# 4_pin_plank.net
KiCad netlist of a schematic drawn in EAGLE
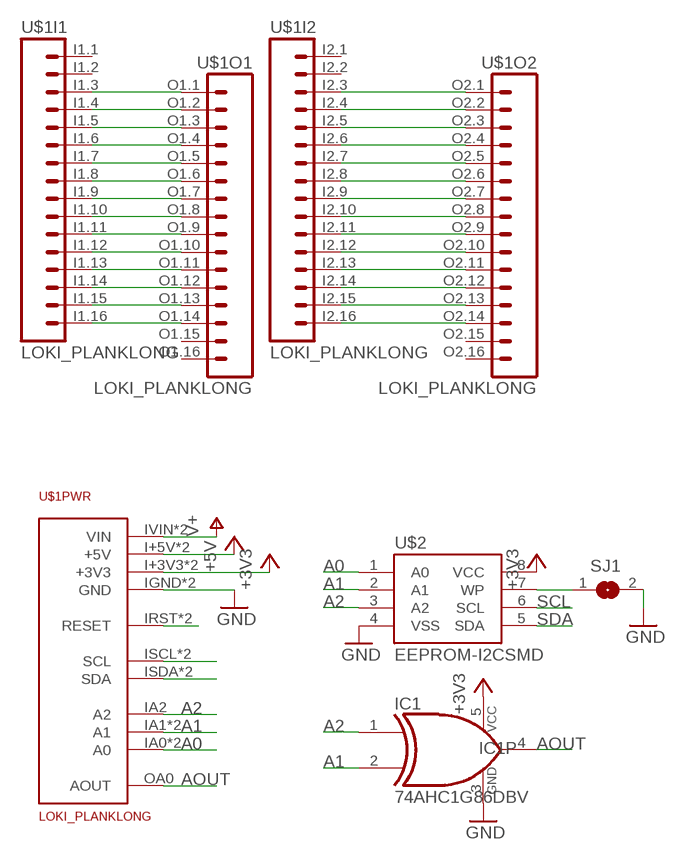
[diagram p0: schematic, sheet 1]

(export (version "E")
  (design (tool "Eeschema 10.0.6"))
  (components
    (comp (ref "IC1")
      (value "74AHC1G86DBV")
      (footprint "eagle-import:SOT23-5")
      (libsource (lib "eagle-import") (part "741G86DBVAHC"))
    )
    (comp (ref "SJ1") (value "SJ") (footprint "eagle-import:SJ") (libsource (lib "eagle-import") (part "SJ")))
    (comp (ref "U$1")
      (value "LOKI_PLANKLONG")
      (footprint "eagle-import:PLANK_LONG")
      (libsource (lib "eagle-import") (part "LOKI_PLANKLONG"))
    )
    (comp (ref "U$2")
      (value "EEPROM-I2CSMD")
      (footprint "eagle-import:SO08")
      (libsource (lib "eagle-import") (part "EEPROM-I2CSMD"))
    )
  )
  (nets
    (net (code "1") (name "+3V3") (class "Default")
      (node (ref "IC1") (pin "5") (pinfunction "VCC_5") (pintype "power_in"))
      (node (ref "U$1") (pin "I+3V3") (pinfunction "+3V3_I+3V3") (pintype "power_in"))
      (node (ref "U$1") (pin "O+3V3") (pinfunction "+3V3_O+3V3") (pintype "power_in"))
      (node (ref "U$2") (pin "8") (pinfunction "VCC_8") (pintype "power_in"))
    )
    (net (code "2") (name "+5V") (class "Default")
      (node (ref "U$1") (pin "I+5V") (pinfunction "+5V_I+5V") (pintype "power_in"))
      (node (ref "U$1") (pin "O+5V") (pinfunction "+5V_O+5V") (pintype "power_in"))
    )
    (net (code "3") (name "/A0") (class "Default")
      (node (ref "U$1") (pin "IA0") (pinfunction "A0_IA0") (pintype "output"))
      (node (ref "U$1") (pin "OA1") (pinfunction "A0_OA1") (pintype "output"))
      (node (ref "U$2") (pin "1") (pinfunction "A0_1") (pintype "bidirectional"))
    )
    (net (code "4") (name "/A1") (class "Default")
      (node (ref "IC1") (pin "2") (pinfunction "I1_2") (pintype "input"))
      (node (ref "U$1") (pin "IA1") (pinfunction "A1_IA1") (pintype "output"))
      (node (ref "U$1") (pin "OA2") (pinfunction "A1_OA2") (pintype "output"))
      (node (ref "U$2") (pin "2") (pinfunction "A1_2") (pintype "bidirectional"))
    )
    (net (code "5") (name "/A2") (class "Default")
      (node (ref "IC1") (pin "1") (pinfunction "I0_1") (pintype "input"))
      (node (ref "U$1") (pin "IA2") (pinfunction "A2_IA2") (pintype "output"))
      (node (ref "U$2") (pin "3") (pinfunction "A2_3") (pintype "bidirectional"))
    )
    (net (code "6") (name "/AOUT") (class "Default")
      (node (ref "IC1") (pin "4") (pinfunction "O_4") (pintype "output"))
      (node (ref "U$1") (pin "OA0") (pinfunction "AOUT_OA0") (pintype "input"))
    )
    (net (code "7") (name "/SCL") (class "Default")
      (node (ref "U$1") (pin "ISCL") (pinfunction "SCL_ISCL") (pintype "bidirectional"))
      (node (ref "U$1") (pin "OSCL") (pinfunction "SCL_OSCL") (pintype "bidirectional"))
      (node (ref "U$2") (pin "6") (pinfunction "SCL_6") (pintype "bidirectional"))
    )
    (net (code "8") (name "/SDA") (class "Default")
      (node (ref "U$1") (pin "ISDA") (pinfunction "SDA_ISDA") (pintype "bidirectional"))
      (node (ref "U$1") (pin "OSDA") (pinfunction "SDA_OSDA") (pintype "bidirectional"))
      (node (ref "U$2") (pin "5") (pinfunction "SDA_5") (pintype "bidirectional"))
    )
    (net (code "9") (name "GND") (class "Default")
      (node (ref "IC1") (pin "3") (pinfunction "GND_3") (pintype "power_in"))
      (node (ref "SJ1") (pin "2") (pinfunction "2_2") (pintype "passive"))
      (node (ref "U$1") (pin "IGND") (pinfunction "GND_IGND") (pintype "power_in"))
      (node (ref "U$1") (pin "OGND") (pinfunction "GND_OGND") (pintype "power_in"))
      (node (ref "U$2") (pin "4") (pinfunction "VSS_4") (pintype "power_in"))
    )
    (net (code "10") (name "Net-(U$1A-3)") (class "Default")
      (node (ref "U$1") (pin "I1.3") (pinfunction "3_I1.3") (pintype "passive"))
      (node (ref "U$1") (pin "O1.1") (pinfunction "1_O1.1") (pintype "passive"))
    )
    (net (code "11") (name "Net-(U$1A-4)") (class "Default")
      (node (ref "U$1") (pin "I1.4") (pinfunction "4_I1.4") (pintype "passive"))
      (node (ref "U$1") (pin "O1.2") (pinfunction "2_O1.2") (pintype "passive"))
    )
    (net (code "12") (name "Net-(U$1A-5)") (class "Default")
      (node (ref "U$1") (pin "I1.5") (pinfunction "5_I1.5") (pintype "passive"))
      (node (ref "U$1") (pin "O1.3") (pinfunction "3_O1.3") (pintype "passive"))
    )
    (net (code "13") (name "Net-(U$1A-6)") (class "Default")
      (node (ref "U$1") (pin "I1.6") (pinfunction "6_I1.6") (pintype "passive"))
      (node (ref "U$1") (pin "O1.4") (pinfunction "4_O1.4") (pintype "passive"))
    )
    (net (code "14") (name "Net-(U$1A-7)") (class "Default")
      (node (ref "U$1") (pin "I1.7") (pinfunction "7_I1.7") (pintype "passive"))
      (node (ref "U$1") (pin "O1.5") (pinfunction "5_O1.5") (pintype "passive"))
    )
    (net (code "15") (name "Net-(U$1A-8)") (class "Default")
      (node (ref "U$1") (pin "I1.8") (pinfunction "8_I1.8") (pintype "passive"))
      (node (ref "U$1") (pin "O1.6") (pinfunction "6_O1.6") (pintype "passive"))
    )
    (net (code "16") (name "Net-(U$1A-9)") (class "Default")
      (node (ref "U$1") (pin "I1.9") (pinfunction "9_I1.9") (pintype "passive"))
      (node (ref "U$1") (pin "O1.7") (pinfunction "7_O1.7") (pintype "passive"))
    )
    (net (code "17") (name "Net-(U$1A-10)") (class "Default")
      (node (ref "U$1") (pin "I1.10") (pinfunction "10_I1.10") (pintype "passive"))
      (node (ref "U$1") (pin "O1.8") (pinfunction "8_O1.8") (pintype "passive"))
    )
    (net (code "18") (name "Net-(U$1A-11)") (class "Default")
      (node (ref "U$1") (pin "I1.11") (pinfunction "11_I1.11") (pintype "passive"))
      (node (ref "U$1") (pin "O1.9") (pinfunction "9_O1.9") (pintype "passive"))
    )
    (net (code "19") (name "Net-(U$1A-12)") (class "Default")
      (node (ref "U$1") (pin "I1.12") (pinfunction "12_I1.12") (pintype "passive"))
      (node (ref "U$1") (pin "O1.10") (pinfunction "10_O1.10") (pintype "passive"))
    )
    (net (code "20") (name "Net-(U$1A-13)") (class "Default")
      (node (ref "U$1") (pin "I1.13") (pinfunction "13_I1.13") (pintype "passive"))
      (node (ref "U$1") (pin "O1.11") (pinfunction "11_O1.11") (pintype "passive"))
    )
    (net (code "21") (name "Net-(U$1A-14)") (class "Default")
      (node (ref "U$1") (pin "I1.14") (pinfunction "14_I1.14") (pintype "passive"))
      (node (ref "U$1") (pin "O1.12") (pinfunction "12_O1.12") (pintype "passive"))
    )
    (net (code "22") (name "Net-(U$1A-15)") (class "Default")
      (node (ref "U$1") (pin "I1.15") (pinfunction "15_I1.15") (pintype "passive"))
      (node (ref "U$1") (pin "O1.13") (pinfunction "13_O1.13") (pintype "passive"))
    )
    (net (code "23") (name "Net-(U$1A-16)") (class "Default")
      (node (ref "U$1") (pin "I1.16") (pinfunction "16_I1.16") (pintype "passive"))
      (node (ref "U$1") (pin "O1.14") (pinfunction "14_O1.14") (pintype "passive"))
    )
    (net (code "24") (name "Net-(U$1B-3)") (class "Default")
      (node (ref "U$1") (pin "I2.3") (pinfunction "3_I2.3") (pintype "passive"))
      (node (ref "U$1") (pin "O2.1") (pinfunction "1_O2.1") (pintype "passive"))
    )
    (net (code "25") (name "Net-(U$1B-4)") (class "Default")
      (node (ref "U$1") (pin "I2.4") (pinfunction "4_I2.4") (pintype "passive"))
      (node (ref "U$1") (pin "O2.2") (pinfunction "2_O2.2") (pintype "passive"))
    )
    (net (code "26") (name "Net-(U$1B-5)") (class "Default")
      (node (ref "U$1") (pin "I2.5") (pinfunction "5_I2.5") (pintype "passive"))
      (node (ref "U$1") (pin "O2.3") (pinfunction "3_O2.3") (pintype "passive"))
    )
    (net (code "27") (name "Net-(U$1B-6)") (class "Default")
      (node (ref "U$1") (pin "I2.6") (pinfunction "6_I2.6") (pintype "passive"))
      (node (ref "U$1") (pin "O2.4") (pinfunction "4_O2.4") (pintype "passive"))
    )
    (net (code "28") (name "Net-(U$1B-7)") (class "Default")
      (node (ref "U$1") (pin "I2.7") (pinfunction "7_I2.7") (pintype "passive"))
      (node (ref "U$1") (pin "O2.5") (pinfunction "5_O2.5") (pintype "passive"))
    )
    (net (code "29") (name "Net-(U$1B-8)") (class "Default")
      (node (ref "U$1") (pin "I2.8") (pinfunction "8_I2.8") (pintype "passive"))
      (node (ref "U$1") (pin "O2.6") (pinfunction "6_O2.6") (pintype "passive"))
    )
    (net (code "30") (name "Net-(U$1B-9)") (class "Default")
      (node (ref "U$1") (pin "I2.9") (pinfunction "9_I2.9") (pintype "passive"))
      (node (ref "U$1") (pin "O2.7") (pinfunction "7_O2.7") (pintype "passive"))
    )
    (net (code "31") (name "Net-(U$1B-10)") (class "Default")
      (node (ref "U$1") (pin "I2.10") (pinfunction "10_I2.10") (pintype "passive"))
      (node (ref "U$1") (pin "O2.8") (pinfunction "8_O2.8") (pintype "passive"))
    )
    (net (code "32") (name "Net-(U$1B-11)") (class "Default")
      (node (ref "U$1") (pin "I2.11") (pinfunction "11_I2.11") (pintype "passive"))
      (node (ref "U$1") (pin "O2.9") (pinfunction "9_O2.9") (pintype "passive"))
    )
    (net (code "33") (name "Net-(U$1B-12)") (class "Default")
      (node (ref "U$1") (pin "I2.12") (pinfunction "12_I2.12") (pintype "passive"))
      (node (ref "U$1") (pin "O2.10") (pinfunction "10_O2.10") (pintype "passive"))
    )
    (net (code "34") (name "Net-(U$1B-13)") (class "Default")
      (node (ref "U$1") (pin "I2.13") (pinfunction "13_I2.13") (pintype "passive"))
      (node (ref "U$1") (pin "O2.11") (pinfunction "11_O2.11") (pintype "passive"))
    )
    (net (code "35") (name "Net-(U$1B-14)") (class "Default")
      (node (ref "U$1") (pin "I2.14") (pinfunction "14_I2.14") (pintype "passive"))
      (node (ref "U$1") (pin "O2.12") (pinfunction "12_O2.12") (pintype "passive"))
    )
    (net (code "36") (name "Net-(U$1B-15)") (class "Default")
      (node (ref "U$1") (pin "I2.15") (pinfunction "15_I2.15") (pintype "passive"))
      (node (ref "U$1") (pin "O2.13") (pinfunction "13_O2.13") (pintype "passive"))
    )
    (net (code "37") (name "Net-(U$1B-16)") (class "Default")
      (node (ref "U$1") (pin "I2.16") (pinfunction "16_I2.16") (pintype "passive"))
      (node (ref "U$1") (pin "O2.14") (pinfunction "14_O2.14") (pintype "passive"))
    )
    (net (code "38") (name "Net-(U$1E-RESET-PadIRST)") (class "Default")
      (node (ref "U$1") (pin "IRST") (pinfunction "RESET_IRST") (pintype "input"))
      (node (ref "U$1") (pin "ORST") (pinfunction "RESET_ORST") (pintype "input"))
    )
    (net (code "39") (name "Net-(U$2-WP)") (class "Default")
      (node (ref "SJ1") (pin "1") (pinfunction "1_1") (pintype "passive"))
      (node (ref "U$2") (pin "7") (pinfunction "WP_7") (pintype "bidirectional"))
    )
    (net (code "40") (name "V+") (class "Default")
      (node (ref "U$1") (pin "IVIN") (pinfunction "VIN_IVIN") (pintype "power_in"))
      (node (ref "U$1") (pin "OVIN") (pinfunction "VIN_OVIN") (pintype "power_in"))
    )
    (net (code "41") (name "unconnected-(U$1A-1-PadI1.1)") (class "Default")
      (node (ref "U$1") (pin "I1.1") (pinfunction "1_I1.1") (pintype "passive"))
    )
    (net (code "42") (name "unconnected-(U$1A-2-PadI1.2)") (class "Default")
      (node (ref "U$1") (pin "I1.2") (pinfunction "2_I1.2") (pintype "passive"))
    )
    (net (code "43") (name "unconnected-(U$1B-1-PadI2.1)") (class "Default")
      (node (ref "U$1") (pin "I2.1") (pinfunction "1_I2.1") (pintype "passive"))
    )
    (net (code "44") (name "unconnected-(U$1B-2-PadI2.2)") (class "Default")
      (node (ref "U$1") (pin "I2.2") (pinfunction "2_I2.2") (pintype "passive"))
    )
    (net (code "45") (name "unconnected-(U$1C-15-PadO1.15)") (class "Default")
      (node (ref "U$1") (pin "O1.15") (pinfunction "15_O1.15") (pintype "passive"))
    )
    (net (code "46") (name "unconnected-(U$1C-16-PadO1.16)") (class "Default")
      (node (ref "U$1") (pin "O1.16") (pinfunction "16_O1.16") (pintype "passive"))
    )
    (net (code "47") (name "unconnected-(U$1D-15-PadO2.15)") (class "Default")
      (node (ref "U$1") (pin "O2.15") (pinfunction "15_O2.15") (pintype "passive"))
    )
    (net (code "48") (name "unconnected-(U$1D-16-PadO2.16)") (class "Default")
      (node (ref "U$1") (pin "O2.16") (pinfunction "16_O2.16") (pintype "passive"))
    )
  )
)
